# LcsNodes-Diagnostic-Board-B_02_00.net
KiCad netlist of a schematic drawn in EasyEDA
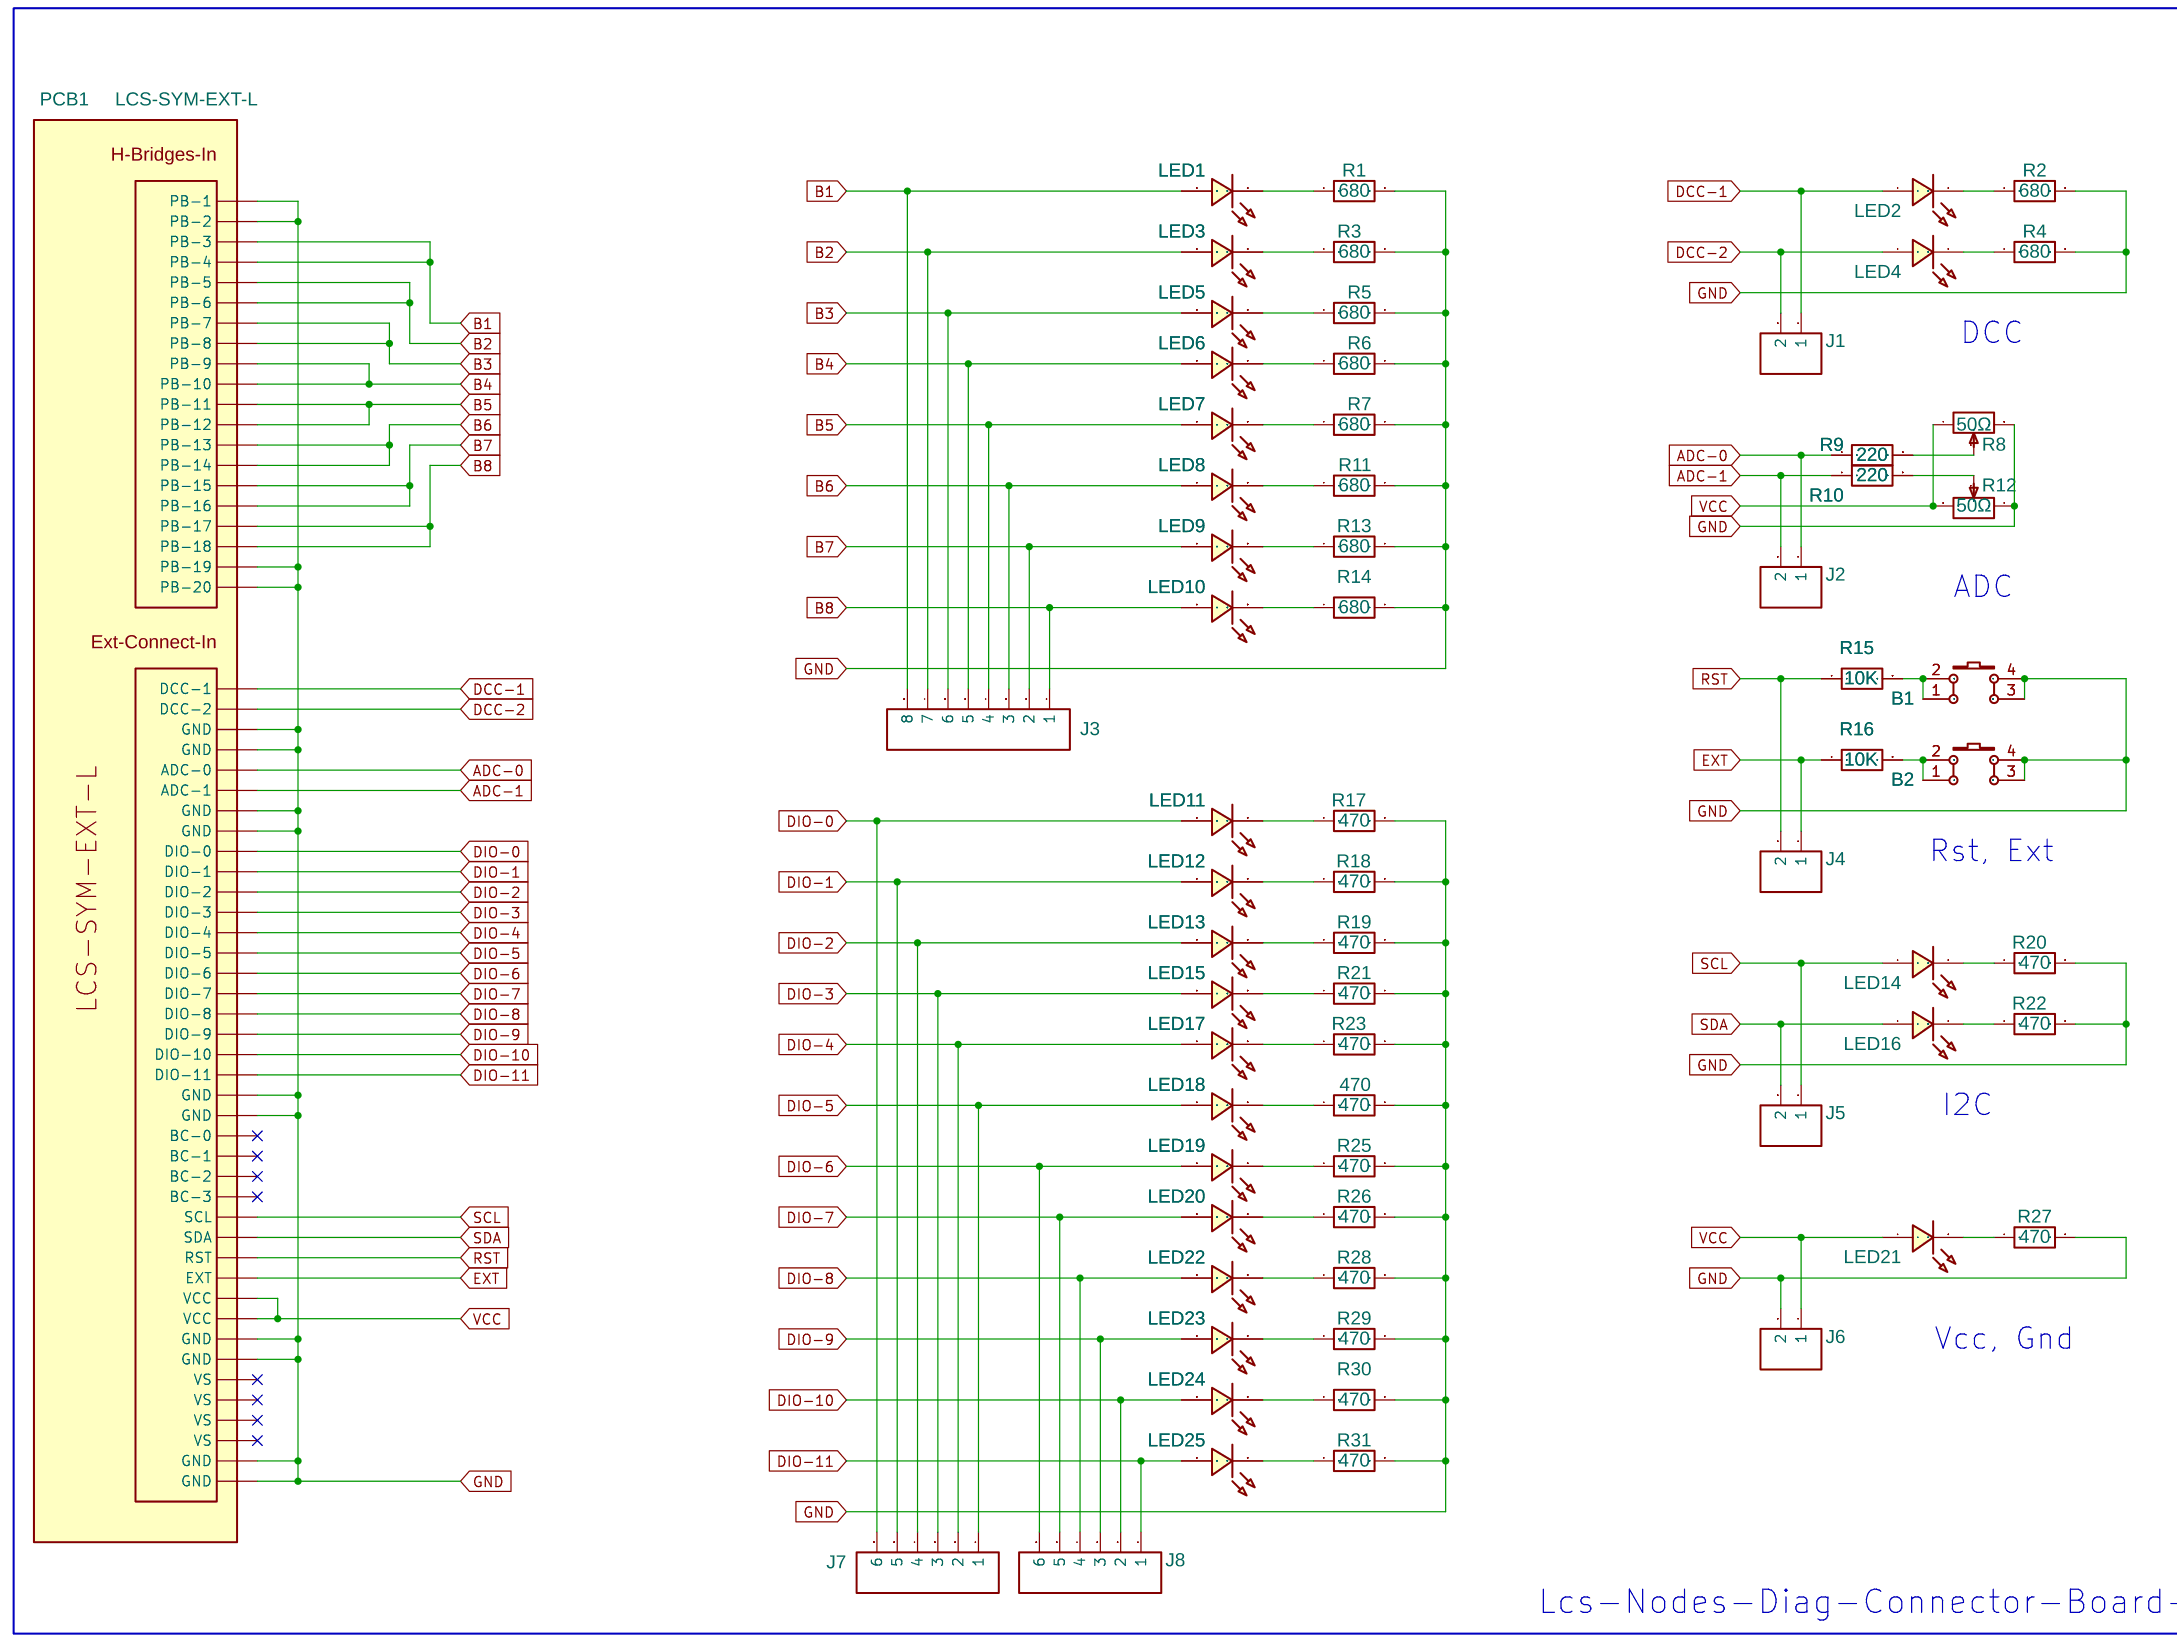
[diagram p0: schematic sheet]

(export (version "E")
  (design (tool "Eeschema 10.0.6"))
  (components
    (comp (ref "470") (value "470") (libsource (lib "") (part "R_0805_EU_1")))
    (comp (ref "B1")
      (value "Opt")
      (fields (field (name "Manufacturer Part") "K2-1102DP-E4SW-04") (field (name "Manufacturer") "韩国韩荣"))
      (libsource (lib "") (part "K4-6×6_TH"))
    )
    (comp (ref "B2")
      (value "Opt")
      (fields (field (name "Manufacturer Part") "K2-1102DP-E4SW-04") (field (name "Manufacturer") "韩国韩荣"))
      (libsource (lib "") (part "K4-6×6_TH"))
    )
    (comp (ref "J1") (value "HDR-M-2.54_1x2") (libsource (lib "") (part "HDR-M-2.54_1x2")))
    (comp (ref "J2") (value "HDR-M-2.54_1x2") (libsource (lib "") (part "HDR-M-2.54_1x2")))
    (comp (ref "J3") (value "HDR-M-2.54_1x8") (libsource (lib "") (part "HDR-M-2.54_1x8")))
    (comp (ref "J4") (value "HDR-M-2.54_1x2") (libsource (lib "") (part "HDR-M-2.54_1x2")))
    (comp (ref "J5") (value "HDR-M-2.54_1x2") (libsource (lib "") (part "HDR-M-2.54_1x2")))
    (comp (ref "J6") (value "HDR-M-2.54_1x2") (libsource (lib "") (part "HDR-M-2.54_1x2")))
    (comp (ref "J7") (value "HDR-M-2.54_1x6") (libsource (lib "") (part "HDR-M-2.54_1x6")))
    (comp (ref "J8") (value "HDR-M-2.54_1x6") (libsource (lib "") (part "HDR-M-2.54_1x6")))
    (comp (ref "LED1")
      (value "LED-0805_G")
      (fields (field (name "Manufacturer Part") "NCD0805G1") (field (name "Manufacturer") "国星光电"))
      (libsource (lib "") (part "LED-0805_G"))
    )
    (comp (ref "LED2")
      (value "LED-0805_G")
      (fields (field (name "Manufacturer Part") "NCD0805G1") (field (name "Manufacturer") "国星光电"))
      (libsource (lib "") (part "LED-0805_G"))
    )
    (comp (ref "LED3")
      (value "LED-0805_G")
      (fields (field (name "Manufacturer Part") "NCD0805G1") (field (name "Manufacturer") "国星光电"))
      (libsource (lib "") (part "LED-0805_G"))
    )
    (comp (ref "LED4")
      (value "LED-0805_G")
      (fields (field (name "Manufacturer Part") "NCD0805G1") (field (name "Manufacturer") "国星光电"))
      (libsource (lib "") (part "LED-0805_G"))
    )
    (comp (ref "LED5")
      (value "LED-0805_G")
      (fields (field (name "Manufacturer Part") "NCD0805G1") (field (name "Manufacturer") "国星光电"))
      (libsource (lib "") (part "LED-0805_G"))
    )
    (comp (ref "LED6")
      (value "LED-0805_G")
      (fields (field (name "Manufacturer Part") "NCD0805G1") (field (name "Manufacturer") "国星光电"))
      (libsource (lib "") (part "LED-0805_G"))
    )
    (comp (ref "LED7")
      (value "LED-0805_G")
      (fields (field (name "Manufacturer Part") "NCD0805G1") (field (name "Manufacturer") "国星光电"))
      (libsource (lib "") (part "LED-0805_G"))
    )
    (comp (ref "LED8")
      (value "LED-0805_G")
      (fields (field (name "Manufacturer Part") "NCD0805G1") (field (name "Manufacturer") "国星光电"))
      (libsource (lib "") (part "LED-0805_G"))
    )
    (comp (ref "LED9")
      (value "LED-0805_G")
      (fields (field (name "Manufacturer Part") "NCD0805G1") (field (name "Manufacturer") "国星光电"))
      (libsource (lib "") (part "LED-0805_G"))
    )
    (comp (ref "LED10")
      (value "LED-0805_G")
      (fields (field (name "Manufacturer Part") "NCD0805G1") (field (name "Manufacturer") "国星光电"))
      (libsource (lib "") (part "LED-0805_G"))
    )
    (comp (ref "LED11")
      (value "LED-0805_G")
      (fields (field (name "Manufacturer Part") "NCD0805G1") (field (name "Manufacturer") "国星光电"))
      (libsource (lib "") (part "LED-0805_G"))
    )
    (comp (ref "LED12")
      (value "LED-0805_G")
      (fields (field (name "Manufacturer Part") "NCD0805G1") (field (name "Manufacturer") "国星光电"))
      (libsource (lib "") (part "LED-0805_G"))
    )
    (comp (ref "LED13")
      (value "LED-0805_G")
      (fields (field (name "Manufacturer Part") "NCD0805G1") (field (name "Manufacturer") "国星光电"))
      (libsource (lib "") (part "LED-0805_G"))
    )
    (comp (ref "LED14")
      (value "LED-0805_G")
      (fields (field (name "Manufacturer Part") "NCD0805G1") (field (name "Manufacturer") "国星光电"))
      (libsource (lib "") (part "LED-0805_G"))
    )
    (comp (ref "LED15")
      (value "LED-0805_G")
      (fields (field (name "Manufacturer Part") "NCD0805G1") (field (name "Manufacturer") "国星光电"))
      (libsource (lib "") (part "LED-0805_G"))
    )
    (comp (ref "LED16")
      (value "LED-0805_G")
      (fields (field (name "Manufacturer Part") "NCD0805G1") (field (name "Manufacturer") "国星光电"))
      (libsource (lib "") (part "LED-0805_G"))
    )
    (comp (ref "LED17")
      (value "LED-0805_G")
      (fields (field (name "Manufacturer Part") "NCD0805G1") (field (name "Manufacturer") "国星光电"))
      (libsource (lib "") (part "LED-0805_G"))
    )
    (comp (ref "LED18")
      (value "LED-0805_G")
      (fields (field (name "Manufacturer Part") "NCD0805G1") (field (name "Manufacturer") "国星光电"))
      (libsource (lib "") (part "LED-0805_G"))
    )
    (comp (ref "LED19")
      (value "LED-0805_G")
      (fields (field (name "Manufacturer Part") "NCD0805G1") (field (name "Manufacturer") "国星光电"))
      (libsource (lib "") (part "LED-0805_G"))
    )
    (comp (ref "LED20")
      (value "LED-0805_G")
      (fields (field (name "Manufacturer Part") "NCD0805G1") (field (name "Manufacturer") "国星光电"))
      (libsource (lib "") (part "LED-0805_G"))
    )
    (comp (ref "LED21")
      (value "LED-0805_G")
      (fields (field (name "Manufacturer Part") "NCD0805G1") (field (name "Manufacturer") "国星光电"))
      (libsource (lib "") (part "LED-0805_G"))
    )
    (comp (ref "LED22")
      (value "LED-0805_G")
      (fields (field (name "Manufacturer Part") "NCD0805G1") (field (name "Manufacturer") "国星光电"))
      (libsource (lib "") (part "LED-0805_G"))
    )
    (comp (ref "LED23")
      (value "LED-0805_G")
      (fields (field (name "Manufacturer Part") "NCD0805G1") (field (name "Manufacturer") "国星光电"))
      (libsource (lib "") (part "LED-0805_G"))
    )
    (comp (ref "LED24")
      (value "LED-0805_G")
      (fields (field (name "Manufacturer Part") "NCD0805G1") (field (name "Manufacturer") "国星光电"))
      (libsource (lib "") (part "LED-0805_G"))
    )
    (comp (ref "LED25")
      (value "LED-0805_G")
      (fields (field (name "Manufacturer Part") "NCD0805G1") (field (name "Manufacturer") "国星光电"))
      (libsource (lib "") (part "LED-0805_G"))
    )
    (comp (ref "PCB1") (value "LCS-SYM-EXT-L") (libsource (lib "") (part "LCS-SYM-EXT-L")))
    (comp (ref "R1") (value "680") (libsource (lib "") (part "R_0805_EU")))
    (comp (ref "R2") (value "680") (libsource (lib "") (part "R_0805_EU")))
    (comp (ref "R3") (value "680") (libsource (lib "") (part "R_0805_EU")))
    (comp (ref "R4") (value "680") (libsource (lib "") (part "R_0805_EU")))
    (comp (ref "R5") (value "680") (libsource (lib "") (part "R_0805_EU")))
    (comp (ref "R6") (value "680") (libsource (lib "") (part "R_0805_EU")))
    (comp (ref "R7") (value "680") (libsource (lib "") (part "R_0805_EU")))
    (comp (ref "R8")
      (value "50Ω")
      (fields
        (field (name "Manufacturer Part") "Precision potentiometer 3296W/50ohm")
        (field (name "Manufacturer") "ReliaPro")
      )
      (libsource (lib "") (part "Precision potentiometer 3296W/50ohm"))
    )
    (comp (ref "R9") (value "220") (libsource (lib "") (part "R_0805_EU")))
    (comp (ref "R10") (value "220") (libsource (lib "") (part "R_0805_EU")))
    (comp (ref "R11") (value "680") (libsource (lib "") (part "R_0805_EU")))
    (comp (ref "R12")
      (value "50Ω")
      (fields
        (field (name "Manufacturer Part") "Precision potentiometer 3296W/50ohm")
        (field (name "Manufacturer") "ReliaPro")
      )
      (libsource (lib "") (part "Precision potentiometer 3296W/50ohm_1"))
    )
    (comp (ref "R13") (value "680") (libsource (lib "") (part "R_0805_EU")))
    (comp (ref "R14") (value "680") (libsource (lib "") (part "R_0805_EU")))
    (comp (ref "R15") (value "10K") (libsource (lib "") (part "R_0805_EU")))
    (comp (ref "R16") (value "10K") (libsource (lib "") (part "R_0805_EU")))
    (comp (ref "R17") (value "470") (libsource (lib "") (part "R_0805_EU")))
    (comp (ref "R18") (value "470") (libsource (lib "") (part "R_0805_EU")))
    (comp (ref "R19") (value "470") (libsource (lib "") (part "R_0805_EU")))
    (comp (ref "R20") (value "470") (libsource (lib "") (part "R_0805_EU")))
    (comp (ref "R21") (value "470") (libsource (lib "") (part "R_0805_EU")))
    (comp (ref "R22") (value "470") (libsource (lib "") (part "R_0805_EU")))
    (comp (ref "R23") (value "470") (libsource (lib "") (part "R_0805_EU")))
    (comp (ref "R25") (value "470") (libsource (lib "") (part "R_0805_EU")))
    (comp (ref "R26") (value "470") (libsource (lib "") (part "R_0805_EU")))
    (comp (ref "R27") (value "470") (libsource (lib "") (part "R_0805_EU")))
    (comp (ref "R28") (value "470") (libsource (lib "") (part "R_0805_EU")))
    (comp (ref "R29") (value "470") (libsource (lib "") (part "R_0805_EU")))
    (comp (ref "R30") (value "470") (libsource (lib "") (part "R_0805_EU")))
    (comp (ref "R31") (value "470") (libsource (lib "") (part "R_0805_EU")))
  )
  (nets
    (net (code "1") (name "ADC-0") (class "Default")
      (node (ref "J2") (pin "1") (pinfunction "1_1") (pintype "unspecified"))
      (node (ref "PCB1") (pin "64") (pinfunction "ADC-0_64") (pintype "unspecified"))
      (node (ref "R9") (pin "1") (pinfunction "1_1") (pintype "unspecified"))
    )
    (net (code "2") (name "ADC-1") (class "Default")
      (node (ref "J2") (pin "2") (pinfunction "2_2") (pintype "unspecified"))
      (node (ref "PCB1") (pin "65") (pinfunction "ADC-1_65") (pintype "unspecified"))
      (node (ref "R10") (pin "1") (pinfunction "1_1") (pintype "unspecified"))
    )
    (net (code "3") (name "B1") (class "Default")
      (node (ref "J3") (pin "8") (pinfunction "8_8") (pintype "unspecified"))
      (node (ref "LED1") (pin "1") (pinfunction "1_1") (pintype "unspecified"))
      (node (ref "PCB1") (pin "32") (pinfunction "PB-3_32") (pintype "unspecified"))
      (node (ref "PCB1") (pin "33") (pinfunction "PB-4_33") (pintype "unspecified"))
    )
    (net (code "4") (name "B2") (class "Default")
      (node (ref "J3") (pin "7") (pinfunction "7_7") (pintype "unspecified"))
      (node (ref "LED3") (pin "1") (pinfunction "1_1") (pintype "unspecified"))
      (node (ref "PCB1") (pin "34") (pinfunction "PB-5_34") (pintype "unspecified"))
      (node (ref "PCB1") (pin "35") (pinfunction "PB-6_35") (pintype "unspecified"))
    )
    (net (code "5") (name "B3") (class "Default")
      (node (ref "J3") (pin "6") (pinfunction "6_6") (pintype "unspecified"))
      (node (ref "LED5") (pin "1") (pinfunction "1_1") (pintype "unspecified"))
      (node (ref "PCB1") (pin "36") (pinfunction "PB-7_36") (pintype "unspecified"))
      (node (ref "PCB1") (pin "37") (pinfunction "PB-8_37") (pintype "unspecified"))
    )
    (net (code "6") (name "B4") (class "Default")
      (node (ref "J3") (pin "5") (pinfunction "5_5") (pintype "unspecified"))
      (node (ref "LED6") (pin "1") (pinfunction "1_1") (pintype "unspecified"))
      (node (ref "PCB1") (pin "38") (pinfunction "PB-9_38") (pintype "unspecified"))
      (node (ref "PCB1") (pin "39") (pinfunction "PB-10_39") (pintype "unspecified"))
    )
    (net (code "7") (name "B5") (class "Default")
      (node (ref "J3") (pin "4") (pinfunction "4_4") (pintype "unspecified"))
      (node (ref "LED7") (pin "1") (pinfunction "1_1") (pintype "unspecified"))
      (node (ref "PCB1") (pin "40") (pinfunction "PB-11_40") (pintype "unspecified"))
      (node (ref "PCB1") (pin "41") (pinfunction "PB-12_41") (pintype "unspecified"))
    )
    (net (code "8") (name "B6") (class "Default")
      (node (ref "J3") (pin "3") (pinfunction "3_3") (pintype "unspecified"))
      (node (ref "LED8") (pin "1") (pinfunction "1_1") (pintype "unspecified"))
      (node (ref "PCB1") (pin "42") (pinfunction "PB-13_42") (pintype "unspecified"))
      (node (ref "PCB1") (pin "43") (pinfunction "PB-14_43") (pintype "unspecified"))
    )
    (net (code "9") (name "B7") (class "Default")
      (node (ref "J3") (pin "2") (pinfunction "2_2") (pintype "unspecified"))
      (node (ref "LED9") (pin "1") (pinfunction "1_1") (pintype "unspecified"))
      (node (ref "PCB1") (pin "44") (pinfunction "PB-15_44") (pintype "unspecified"))
      (node (ref "PCB1") (pin "45") (pinfunction "PB-16_45") (pintype "unspecified"))
    )
    (net (code "10") (name "B8") (class "Default")
      (node (ref "J3") (pin "1") (pinfunction "1_1") (pintype "unspecified"))
      (node (ref "LED10") (pin "1") (pinfunction "1_1") (pintype "unspecified"))
      (node (ref "PCB1") (pin "46") (pinfunction "PB-17_46") (pintype "unspecified"))
      (node (ref "PCB1") (pin "47") (pinfunction "PB-18_47") (pintype "unspecified"))
    )
    (net (code "11") (name "DCC-1") (class "Default")
      (node (ref "J1") (pin "1") (pinfunction "1_1") (pintype "unspecified"))
      (node (ref "LED2") (pin "1") (pinfunction "1_1") (pintype "unspecified"))
      (node (ref "PCB1") (pin "60") (pinfunction "DCC-1_60") (pintype "unspecified"))
    )
    (net (code "12") (name "DCC-2") (class "Default")
      (node (ref "J1") (pin "2") (pinfunction "2_2") (pintype "unspecified"))
      (node (ref "LED4") (pin "1") (pinfunction "1_1") (pintype "unspecified"))
      (node (ref "PCB1") (pin "61") (pinfunction "DCC-2_61") (pintype "unspecified"))
    )
    (net (code "13") (name "DIO-0") (class "Default")
      (node (ref "J7") (pin "6") (pinfunction "6_6") (pintype "input"))
      (node (ref "LED11") (pin "1") (pinfunction "1_1") (pintype "unspecified"))
      (node (ref "PCB1") (pin "68") (pinfunction "DIO-0_68") (pintype "unspecified"))
    )
    (net (code "14") (name "DIO-1") (class "Default")
      (node (ref "J7") (pin "5") (pinfunction "5_5") (pintype "input"))
      (node (ref "LED12") (pin "1") (pinfunction "1_1") (pintype "unspecified"))
      (node (ref "PCB1") (pin "69") (pinfunction "DIO-1_69") (pintype "unspecified"))
    )
    (net (code "15") (name "DIO-2") (class "Default")
      (node (ref "J7") (pin "4") (pinfunction "4_4") (pintype "input"))
      (node (ref "LED13") (pin "1") (pinfunction "1_1") (pintype "unspecified"))
      (node (ref "PCB1") (pin "70") (pinfunction "DIO-2_70") (pintype "unspecified"))
    )
    (net (code "16") (name "DIO-3") (class "Default")
      (node (ref "J7") (pin "3") (pinfunction "3_3") (pintype "input"))
      (node (ref "LED15") (pin "1") (pinfunction "1_1") (pintype "unspecified"))
      (node (ref "PCB1") (pin "71") (pinfunction "DIO-3_71") (pintype "unspecified"))
    )
    (net (code "17") (name "DIO-4") (class "Default")
      (node (ref "J7") (pin "2") (pinfunction "2_2") (pintype "input"))
      (node (ref "LED17") (pin "1") (pinfunction "1_1") (pintype "unspecified"))
      (node (ref "PCB1") (pin "72") (pinfunction "DIO-4_72") (pintype "unspecified"))
    )
    (net (code "18") (name "DIO-5") (class "Default")
      (node (ref "J7") (pin "1") (pinfunction "1_1") (pintype "input"))
      (node (ref "LED18") (pin "1") (pinfunction "1_1") (pintype "unspecified"))
      (node (ref "PCB1") (pin "73") (pinfunction "DIO-5_73") (pintype "unspecified"))
    )
    (net (code "19") (name "DIO-6") (class "Default")
      (node (ref "J8") (pin "6") (pinfunction "6_6") (pintype "input"))
      (node (ref "LED19") (pin "1") (pinfunction "1_1") (pintype "unspecified"))
      (node (ref "PCB1") (pin "74") (pinfunction "DIO-6_74") (pintype "unspecified"))
    )
    (net (code "20") (name "DIO-7") (class "Default")
      (node (ref "J8") (pin "5") (pinfunction "5_5") (pintype "input"))
      (node (ref "LED20") (pin "1") (pinfunction "1_1") (pintype "unspecified"))
      (node (ref "PCB1") (pin "75") (pinfunction "DIO-7_75") (pintype "unspecified"))
    )
    (net (code "21") (name "DIO-8") (class "Default")
      (node (ref "J8") (pin "4") (pinfunction "4_4") (pintype "input"))
      (node (ref "LED22") (pin "1") (pinfunction "1_1") (pintype "unspecified"))
      (node (ref "PCB1") (pin "76") (pinfunction "DIO-8_76") (pintype "unspecified"))
    )
    (net (code "22") (name "DIO-9") (class "Default")
      (node (ref "J8") (pin "3") (pinfunction "3_3") (pintype "input"))
      (node (ref "LED23") (pin "1") (pinfunction "1_1") (pintype "unspecified"))
      (node (ref "PCB1") (pin "77") (pinfunction "DIO-9_77") (pintype "unspecified"))
    )
    (net (code "23") (name "DIO-10") (class "Default")
      (node (ref "J8") (pin "2") (pinfunction "2_2") (pintype "input"))
      (node (ref "LED24") (pin "1") (pinfunction "1_1") (pintype "unspecified"))
      (node (ref "PCB1") (pin "78") (pinfunction "DIO-10_78") (pintype "unspecified"))
    )
    (net (code "24") (name "DIO-11") (class "Default")
      (node (ref "J8") (pin "1") (pinfunction "1_1") (pintype "input"))
      (node (ref "LED25") (pin "1") (pinfunction "1_1") (pintype "unspecified"))
      (node (ref "PCB1") (pin "79") (pinfunction "DIO-11_79") (pintype "unspecified"))
    )
    (net (code "25") (name "EXT") (class "Default")
      (node (ref "J4") (pin "1") (pinfunction "1_1") (pintype "unspecified"))
      (node (ref "PCB1") (pin "89") (pinfunction "EXT_89") (pintype "unspecified"))
      (node (ref "R16") (pin "1") (pinfunction "1_1") (pintype "unspecified"))
    )
    (net (code "26") (name "GND") (class "Default")
      (node (ref "470") (pin "2") (pinfunction "2_2") (pintype "unspecified"))
      (node (ref "B1") (pin "3") (pinfunction "3_3") (pintype "unspecified"))
      (node (ref "B1") (pin "4") (pinfunction "4_4") (pintype "unspecified"))
      (node (ref "B2") (pin "3") (pinfunction "3_3") (pintype "unspecified"))
      (node (ref "B2") (pin "4") (pinfunction "4_4") (pintype "unspecified"))
      (node (ref "J6") (pin "2") (pinfunction "2_2") (pintype "unspecified"))
      (node (ref "PCB1") (pin "30") (pinfunction "PB-1_30") (pintype "unspecified"))
      (node (ref "PCB1") (pin "31") (pinfunction "PB-2_31") (pintype "unspecified"))
      (node (ref "PCB1") (pin "48") (pinfunction "PB-19_48") (pintype "unspecified"))
      (node (ref "PCB1") (pin "49") (pinfunction "PB-20_49") (pintype "unspecified"))
      (node (ref "PCB1") (pin "62") (pinfunction "GND_62") (pintype "unspecified"))
      (node (ref "PCB1") (pin "63") (pinfunction "GND_63") (pintype "unspecified"))
      (node (ref "PCB1") (pin "66") (pinfunction "GND_66") (pintype "unspecified"))
      (node (ref "PCB1") (pin "67") (pinfunction "GND_67") (pintype "unspecified"))
      (node (ref "PCB1") (pin "80") (pinfunction "GND_80") (pintype "unspecified"))
      (node (ref "PCB1") (pin "81") (pinfunction "GND_81") (pintype "unspecified"))
      (node (ref "PCB1") (pin "92") (pinfunction "GND_92") (pintype "unspecified"))
      (node (ref "PCB1") (pin "93") (pinfunction "GND_93") (pintype "unspecified"))
      (node (ref "PCB1") (pin "98") (pinfunction "GND_98") (pintype "unspecified"))
      (node (ref "PCB1") (pin "99") (pinfunction "GND_99") (pintype "unspecified"))
      (node (ref "R1") (pin "2") (pinfunction "2_2") (pintype "unspecified"))
      (node (ref "R11") (pin "2") (pinfunction "2_2") (pintype "unspecified"))
      (node (ref "R12") (pin "1") (pinfunction "1_1") (pintype "input"))
      (node (ref "R13") (pin "2") (pinfunction "2_2") (pintype "unspecified"))
      (node (ref "R14") (pin "2") (pinfunction "2_2") (pintype "unspecified"))
      (node (ref "R17") (pin "2") (pinfunction "2_2") (pintype "unspecified"))
      (node (ref "R18") (pin "2") (pinfunction "2_2") (pintype "unspecified"))
      (node (ref "R19") (pin "2") (pinfunction "2_2") (pintype "unspecified"))
      (node (ref "R2") (pin "2") (pinfunction "2_2") (pintype "unspecified"))
      (node (ref "R20") (pin "2") (pinfunction "2_2") (pintype "unspecified"))
      (node (ref "R21") (pin "2") (pinfunction "2_2") (pintype "unspecified"))
      (node (ref "R22") (pin "2") (pinfunction "2_2") (pintype "unspecified"))
      (node (ref "R23") (pin "2") (pinfunction "2_2") (pintype "unspecified"))
      (node (ref "R25") (pin "2") (pinfunction "2_2") (pintype "unspecified"))
      (node (ref "R26") (pin "2") (pinfunction "2_2") (pintype "unspecified"))
      (node (ref "R27") (pin "2") (pinfunction "2_2") (pintype "unspecified"))
      (node (ref "R28") (pin "2") (pinfunction "2_2") (pintype "unspecified"))
      (node (ref "R29") (pin "2") (pinfunction "2_2") (pintype "unspecified"))
      (node (ref "R3") (pin "2") (pinfunction "2_2") (pintype "unspecified"))
      (node (ref "R30") (pin "2") (pinfunction "2_2") (pintype "unspecified"))
      (node (ref "R31") (pin "2") (pinfunction "2_2") (pintype "unspecified"))
      (node (ref "R4") (pin "2") (pinfunction "2_2") (pintype "unspecified"))
      (node (ref "R5") (pin "2") (pinfunction "2_2") (pintype "unspecified"))
      (node (ref "R6") (pin "2") (pinfunction "2_2") (pintype "unspecified"))
      (node (ref "R7") (pin "2") (pinfunction "2_2") (pintype "unspecified"))
      (node (ref "R8") (pin "3") (pinfunction "3_3") (pintype "input"))
    )
    (net (code "27") (name "Net-(470-Pad1)") (class "Default")
      (node (ref "470") (pin "1") (pinfunction "1_1") (pintype "unspecified"))
      (node (ref "LED18") (pin "2") (pinfunction "2_2") (pintype "unspecified"))
    )
    (net (code "28") (name "Net-(B1-Pad1)") (class "Default")
      (node (ref "B1") (pin "1") (pinfunction "1_1") (pintype "unspecified"))
      (node (ref "B1") (pin "2") (pinfunction "2_2") (pintype "unspecified"))
      (node (ref "R15") (pin "2") (pinfunction "2_2") (pintype "unspecified"))
    )
    (net (code "29") (name "Net-(B2-Pad1)") (class "Default")
      (node (ref "B2") (pin "1") (pinfunction "1_1") (pintype "unspecified"))
      (node (ref "B2") (pin "2") (pinfunction "2_2") (pintype "unspecified"))
      (node (ref "R16") (pin "2") (pinfunction "2_2") (pintype "unspecified"))
    )
    (net (code "30") (name "Net-(LED1-Pad2)") (class "Default")
      (node (ref "LED1") (pin "2") (pinfunction "2_2") (pintype "unspecified"))
      (node (ref "R1") (pin "1") (pinfunction "1_1") (pintype "unspecified"))
    )
    (net (code "31") (name "Net-(LED2-Pad2)") (class "Default")
      (node (ref "LED2") (pin "2") (pinfunction "2_2") (pintype "unspecified"))
      (node (ref "R2") (pin "1") (pinfunction "1_1") (pintype "unspecified"))
    )
    (net (code "32") (name "Net-(LED3-Pad2)") (class "Default")
      (node (ref "LED3") (pin "2") (pinfunction "2_2") (pintype "unspecified"))
      (node (ref "R3") (pin "1") (pinfunction "1_1") (pintype "unspecified"))
    )
    (net (code "33") (name "Net-(LED4-Pad2)") (class "Default")
      (node (ref "LED4") (pin "2") (pinfunction "2_2") (pintype "unspecified"))
      (node (ref "R4") (pin "1") (pinfunction "1_1") (pintype "unspecified"))
    )
    (net (code "34") (name "Net-(LED5-Pad2)") (class "Default")
      (node (ref "LED5") (pin "2") (pinfunction "2_2") (pintype "unspecified"))
      (node (ref "R5") (pin "1") (pinfunction "1_1") (pintype "unspecified"))
    )
    (net (code "35") (name "Net-(LED6-Pad2)") (class "Default")
      (node (ref "LED6") (pin "2") (pinfunction "2_2") (pintype "unspecified"))
      (node (ref "R6") (pin "1") (pinfunction "1_1") (pintype "unspecified"))
    )
    (net (code "36") (name "Net-(LED7-Pad2)") (class "Default")
      (node (ref "LED7") (pin "2") (pinfunction "2_2") (pintype "unspecified"))
      (node (ref "R7") (pin "1") (pinfunction "1_1") (pintype "unspecified"))
    )
    (net (code "37") (name "Net-(LED8-Pad2)") (class "Default")
      (node (ref "LED8") (pin "2") (pinfunction "2_2") (pintype "unspecified"))
      (node (ref "R11") (pin "1") (pinfunction "1_1") (pintype "unspecified"))
    )
    (net (code "38") (name "Net-(LED9-Pad2)") (class "Default")
      (node (ref "LED9") (pin "2") (pinfunction "2_2") (pintype "unspecified"))
      (node (ref "R13") (pin "1") (pinfunction "1_1") (pintype "unspecified"))
    )
    (net (code "39") (name "Net-(LED10-Pad2)") (class "Default")
      (node (ref "LED10") (pin "2") (pinfunction "2_2") (pintype "unspecified"))
      (node (ref "R14") (pin "1") (pinfunction "1_1") (pintype "unspecified"))
    )
    (net (code "40") (name "Net-(LED11-Pad2)") (class "Default")
      (node (ref "LED11") (pin "2") (pinfunction "2_2") (pintype "unspecified"))
      (node (ref "R17") (pin "1") (pinfunction "1_1") (pintype "unspecified"))
    )
    (net (code "41") (name "Net-(LED12-Pad2)") (class "Default")
      (node (ref "LED12") (pin "2") (pinfunction "2_2") (pintype "unspecified"))
      (node (ref "R18") (pin "1") (pinfunction "1_1") (pintype "unspecified"))
    )
    (net (code "42") (name "Net-(LED13-Pad2)") (class "Default")
      (node (ref "LED13") (pin "2") (pinfunction "2_2") (pintype "unspecified"))
      (node (ref "R19") (pin "1") (pinfunction "1_1") (pintype "unspecified"))
    )
    (net (code "43") (name "Net-(LED14-Pad2)") (class "Default")
      (node (ref "LED14") (pin "2") (pinfunction "2_2") (pintype "unspecified"))
      (node (ref "R20") (pin "1") (pinfunction "1_1") (pintype "unspecified"))
    )
    (net (code "44") (name "Net-(LED15-Pad2)") (class "Default")
      (node (ref "LED15") (pin "2") (pinfunction "2_2") (pintype "unspecified"))
      (node (ref "R21") (pin "1") (pinfunction "1_1") (pintype "unspecified"))
    )
    (net (code "45") (name "Net-(LED16-Pad2)") (class "Default")
      (node (ref "LED16") (pin "2") (pinfunction "2_2") (pintype "unspecified"))
      (node (ref "R22") (pin "1") (pinfunction "1_1") (pintype "unspecified"))
    )
    (net (code "46") (name "Net-(LED17-Pad2)") (class "Default")
      (node (ref "LED17") (pin "2") (pinfunction "2_2") (pintype "unspecified"))
      (node (ref "R23") (pin "1") (pinfunction "1_1") (pintype "unspecified"))
    )
    (net (code "47") (name "Net-(LED19-Pad2)") (class "Default")
      (node (ref "LED19") (pin "2") (pinfunction "2_2") (pintype "unspecified"))
      (node (ref "R25") (pin "1") (pinfunction "1_1") (pintype "unspecified"))
    )
    (net (code "48") (name "Net-(LED20-Pad2)") (class "Default")
      (node (ref "LED20") (pin "2") (pinfunction "2_2") (pintype "unspecified"))
      (node (ref "R26") (pin "1") (pinfunction "1_1") (pintype "unspecified"))
    )
    (net (code "49") (name "Net-(LED21-Pad2)") (class "Default")
      (node (ref "LED21") (pin "2") (pinfunction "2_2") (pintype "unspecified"))
      (node (ref "R27") (pin "1") (pinfunction "1_1") (pintype "unspecified"))
    )
    (net (code "50") (name "Net-(LED22-Pad2)") (class "Default")
      (node (ref "LED22") (pin "2") (pinfunction "2_2") (pintype "unspecified"))
      (node (ref "R28") (pin "1") (pinfunction "1_1") (pintype "unspecified"))
    )
    (net (code "51") (name "Net-(LED23-Pad2)") (class "Default")
      (node (ref "LED23") (pin "2") (pinfunction "2_2") (pintype "unspecified"))
      (node (ref "R29") (pin "1") (pinfunction "1_1") (pintype "unspecified"))
    )
    (net (code "52") (name "Net-(LED24-Pad2)") (class "Default")
      (node (ref "LED24") (pin "2") (pinfunction "2_2") (pintype "unspecified"))
      (node (ref "R30") (pin "1") (pinfunction "1_1") (pintype "unspecified"))
    )
    (net (code "53") (name "Net-(LED25-Pad2)") (class "Default")
      (node (ref "LED25") (pin "2") (pinfunction "2_2") (pintype "unspecified"))
      (node (ref "R31") (pin "1") (pinfunction "1_1") (pintype "unspecified"))
    )
    (net (code "54") (name "Net-(R8-Pad2)") (class "Default")
      (node (ref "R8") (pin "2") (pinfunction "2_2") (pintype "input"))
      (node (ref "R9") (pin "2") (pinfunction "2_2") (pintype "unspecified"))
    )
    (net (code "55") (name "Net-(R10-Pad2)") (class "Default")
      (node (ref "R10") (pin "2") (pinfunction "2_2") (pintype "unspecified"))
      (node (ref "R12") (pin "2") (pinfunction "2_2") (pintype "input"))
    )
    (net (code "56") (name "RST") (class "Default")
      (node (ref "J4") (pin "2") (pinfunction "2_2") (pintype "unspecified"))
      (node (ref "PCB1") (pin "88") (pinfunction "RST_88") (pintype "unspecified"))
      (node (ref "R15") (pin "1") (pinfunction "1_1") (pintype "unspecified"))
    )
    (net (code "57") (name "SCL") (class "Default")
      (node (ref "J5") (pin "1") (pinfunction "1_1") (pintype "unspecified"))
      (node (ref "LED14") (pin "1") (pinfunction "1_1") (pintype "unspecified"))
      (node (ref "PCB1") (pin "86") (pinfunction "SCL_86") (pintype "unspecified"))
    )
    (net (code "58") (name "SDA") (class "Default")
      (node (ref "J5") (pin "2") (pinfunction "2_2") (pintype "unspecified"))
      (node (ref "LED16") (pin "1") (pinfunction "1_1") (pintype "unspecified"))
      (node (ref "PCB1") (pin "87") (pinfunction "SDA_87") (pintype "unspecified"))
    )
    (net (code "59") (name "VCC") (class "Default")
      (node (ref "J6") (pin "1") (pinfunction "1_1") (pintype "unspecified"))
      (node (ref "LED21") (pin "1") (pinfunction "1_1") (pintype "unspecified"))
      (node (ref "PCB1") (pin "90") (pinfunction "VCC_90") (pintype "unspecified"))
      (node (ref "PCB1") (pin "91") (pinfunction "VCC_91") (pintype "unspecified"))
      (node (ref "R12") (pin "3") (pinfunction "3_3") (pintype "input"))
      (node (ref "R8") (pin "1") (pinfunction "1_1") (pintype "input"))
    )
    (net (code "60") (name "unconnected-(PCB1-BC-0-Pad82)") (class "Default")
      (node (ref "PCB1") (pin "82") (pinfunction "BC-0_82") (pintype "unspecified+no_connect"))
    )
    (net (code "61") (name "unconnected-(PCB1-BC-1-Pad83)") (class "Default")
      (node (ref "PCB1") (pin "83") (pinfunction "BC-1_83") (pintype "unspecified+no_connect"))
    )
    (net (code "62") (name "unconnected-(PCB1-BC-2-Pad84)") (class "Default")
      (node (ref "PCB1") (pin "84") (pinfunction "BC-2_84") (pintype "unspecified+no_connect"))
    )
    (net (code "63") (name "unconnected-(PCB1-BC-3-Pad85)") (class "Default")
      (node (ref "PCB1") (pin "85") (pinfunction "BC-3_85") (pintype "unspecified+no_connect"))
    )
    (net (code "64") (name "unconnected-(PCB1-VS-Pad94)") (class "Default")
      (node (ref "PCB1") (pin "94") (pinfunction "VS_94") (pintype "unspecified+no_connect"))
    )
    (net (code "65") (name "unconnected-(PCB1-VS-Pad95)") (class "Default")
      (node (ref "PCB1") (pin "95") (pinfunction "VS_95") (pintype "unspecified+no_connect"))
    )
    (net (code "66") (name "unconnected-(PCB1-VS-Pad96)") (class "Default")
      (node (ref "PCB1") (pin "96") (pinfunction "VS_96") (pintype "unspecified+no_connect"))
    )
    (net (code "67") (name "unconnected-(PCB1-VS-Pad97)") (class "Default")
      (node (ref "PCB1") (pin "97") (pinfunction "VS_97") (pintype "unspecified+no_connect"))
    )
  )
)
